# Bootloader_Board.net
KiCad netlist of a schematic drawn in EAGLE
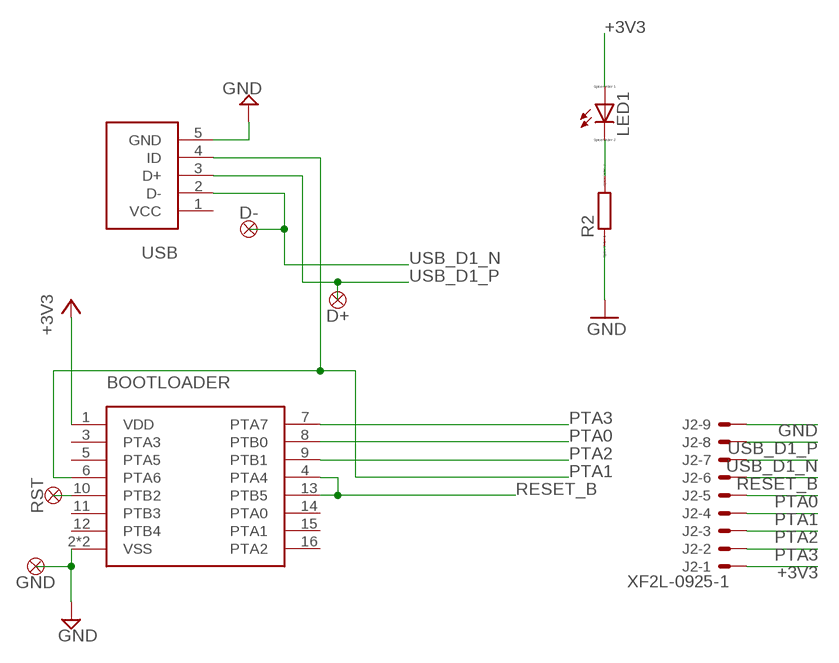
[diagram p0: schematic, sheet 1]

(export (version "E")
  (design (tool "Eeschema 10.0.6"))
  (components
    (comp (ref "BOOTLOADER")
      (value "MKL02Z32CORRECT")
      (footprint "eagle-import:QFN16")
      (libsource (lib "eagle-import") (part "MKL02Z32CORRECT"))
    )
    (comp (ref "D+")
      (value "TESTPAD")
      (footprint "eagle-import:TESTPAD")
      (libsource (lib "eagle-import") (part "TESTPAD"))
    )
    (comp (ref "D-")
      (value "TESTPAD")
      (footprint "eagle-import:TESTPAD")
      (libsource (lib "eagle-import") (part "TESTPAD"))
    )
    (comp (ref "GND")
      (value "TESTPAD")
      (footprint "eagle-import:TESTPAD")
      (libsource (lib "eagle-import") (part "TESTPAD"))
    )
    (comp (ref "J2")
      (value "XF2L-0925-1")
      (footprint "eagle-import:XF2L-0925-1")
      (fields (field (name "MPN") "XF2L-0925-1A"))
      (libsource (lib "eagle-import") (part "XF2-09?25-1L"))
    )
    (comp (ref "LED1")
      (value "LED_ESML0603")
      (footprint "eagle-import:LED_SML0603")
      (libsource (lib "eagle-import") (part "LED_ESML0603"))
    )
    (comp (ref "R2")
      (value "RR0603")
      (footprint "eagle-import:R0603")
      (libsource (lib "eagle-import") (part "RR0603"))
    )
    (comp (ref "RST")
      (value "TESTPAD")
      (footprint "eagle-import:TESTPAD")
      (libsource (lib "eagle-import") (part "TESTPAD"))
    )
    (comp (ref "USB")
      (value "10118194-0001LF")
      (footprint "eagle-import:10118194-0001LF")
      (libsource (lib "eagle-import") (part "10118194-0001LF"))
    )
  )
  (nets
    (net (code "1") (name "+3V3") (class "Default")
      (node (ref "BOOTLOADER") (pin "1") (pinfunction "VDD_1") (pintype "bidirectional"))
      (node (ref "J2") (pin "1") (pinfunction "MSV_1") (pintype "passive"))
      (node (ref "LED1") (pin "A") (pinfunction "A_A") (pintype "passive"))
    )
    (net (code "2") (name "/PTA0") (class "Default")
      (node (ref "BOOTLOADER") (pin "8") (pinfunction "PTB0_8") (pintype "bidirectional"))
      (node (ref "J2") (pin "5") (pinfunction "MS_5") (pintype "passive"))
    )
    (net (code "3") (name "/PTA1") (class "Default")
      (node (ref "BOOTLOADER") (pin "6") (pinfunction "PTA6_6") (pintype "bidirectional"))
      (node (ref "J2") (pin "4") (pinfunction "MS_4") (pintype "passive"))
      (node (ref "USB") (pin "4") (pinfunction "ID_4") (pintype "bidirectional"))
    )
    (net (code "4") (name "/PTA2") (class "Default")
      (node (ref "BOOTLOADER") (pin "9") (pinfunction "PTB1_9") (pintype "bidirectional"))
      (node (ref "J2") (pin "3") (pinfunction "MS_3") (pintype "passive"))
    )
    (net (code "5") (name "/PTA3") (class "Default")
      (node (ref "BOOTLOADER") (pin "7") (pinfunction "PTA7_7") (pintype "bidirectional"))
      (node (ref "J2") (pin "2") (pinfunction "MS_2") (pintype "passive"))
    )
    (net (code "6") (name "/RESET_B") (class "Default")
      (node (ref "BOOTLOADER") (pin "13") (pinfunction "PTB5_13") (pintype "bidirectional"))
      (node (ref "BOOTLOADER") (pin "4") (pinfunction "PTA4_4") (pintype "bidirectional"))
      (node (ref "J2") (pin "6") (pinfunction "MS_6") (pintype "passive"))
    )
    (net (code "7") (name "/USB_D1_N") (class "Default")
      (node (ref "D-") (pin "P$1") (pinfunction "P$1_P$1") (pintype "bidirectional"))
      (node (ref "J2") (pin "7") (pinfunction "MS_7") (pintype "passive"))
      (node (ref "USB") (pin "2") (pinfunction "D-_2") (pintype "bidirectional"))
    )
    (net (code "8") (name "/USB_D1_P") (class "Default")
      (node (ref "D+") (pin "P$1") (pinfunction "P$1_P$1") (pintype "bidirectional"))
      (node (ref "J2") (pin "8") (pinfunction "MS_8") (pintype "passive"))
      (node (ref "USB") (pin "3") (pinfunction "D+_3") (pintype "bidirectional"))
    )
    (net (code "9") (name "GND") (class "Default")
      (node (ref "BOOTLOADER") (pin "2") (pinfunction "VSS_2") (pintype "bidirectional"))
      (node (ref "BOOTLOADER") (pin "TH") (pinfunction "VSS_TH") (pintype "bidirectional"))
      (node (ref "GND") (pin "P$1") (pinfunction "P$1_P$1") (pintype "bidirectional"))
      (node (ref "J2") (pin "9") (pinfunction "MS_9") (pintype "passive"))
      (node (ref "R2") (pin "1") (pinfunction "1_1") (pintype "passive"))
      (node (ref "USB") (pin "5") (pinfunction "GND_5") (pintype "bidirectional"))
    )
    (net (code "10") (name "Net-(BOOTLOADER-PTB2)") (class "Default")
      (node (ref "BOOTLOADER") (pin "10") (pinfunction "PTB2_10") (pintype "bidirectional"))
      (node (ref "RST") (pin "P$1") (pinfunction "P$1_P$1") (pintype "bidirectional"))
    )
    (net (code "11") (name "Net-(LED1-PadC)") (class "Default")
      (node (ref "LED1") (pin "C") (pinfunction "C_C") (pintype "passive"))
      (node (ref "R2") (pin "2") (pinfunction "2_2") (pintype "passive"))
    )
    (net (code "12") (name "unconnected-(BOOTLOADER-PTA0-Pad14)") (class "Default")
      (node (ref "BOOTLOADER") (pin "14") (pinfunction "PTA0_14") (pintype "bidirectional"))
    )
    (net (code "13") (name "unconnected-(BOOTLOADER-PTA1-Pad15)") (class "Default")
      (node (ref "BOOTLOADER") (pin "15") (pinfunction "PTA1_15") (pintype "bidirectional"))
    )
    (net (code "14") (name "unconnected-(BOOTLOADER-PTA2-Pad16)") (class "Default")
      (node (ref "BOOTLOADER") (pin "16") (pinfunction "PTA2_16") (pintype "bidirectional"))
    )
    (net (code "15") (name "unconnected-(BOOTLOADER-PTA3-Pad3)") (class "Default")
      (node (ref "BOOTLOADER") (pin "3") (pinfunction "PTA3_3") (pintype "bidirectional"))
    )
    (net (code "16") (name "unconnected-(BOOTLOADER-PTA5-Pad5)") (class "Default")
      (node (ref "BOOTLOADER") (pin "5") (pinfunction "PTA5_5") (pintype "bidirectional"))
    )
    (net (code "17") (name "unconnected-(BOOTLOADER-PTB3-Pad11)") (class "Default")
      (node (ref "BOOTLOADER") (pin "11") (pinfunction "PTB3_11") (pintype "bidirectional"))
    )
    (net (code "18") (name "unconnected-(BOOTLOADER-PTB4-Pad12)") (class "Default")
      (node (ref "BOOTLOADER") (pin "12") (pinfunction "PTB4_12") (pintype "bidirectional"))
    )
    (net (code "19") (name "unconnected-(USB-VCC-Pad1)") (class "Default")
      (node (ref "USB") (pin "1") (pinfunction "VCC_1") (pintype "bidirectional"))
    )
  )
)
